# Wifi_Relay_V3.net
KiCad netlist of a schematic drawn in Altium Designer
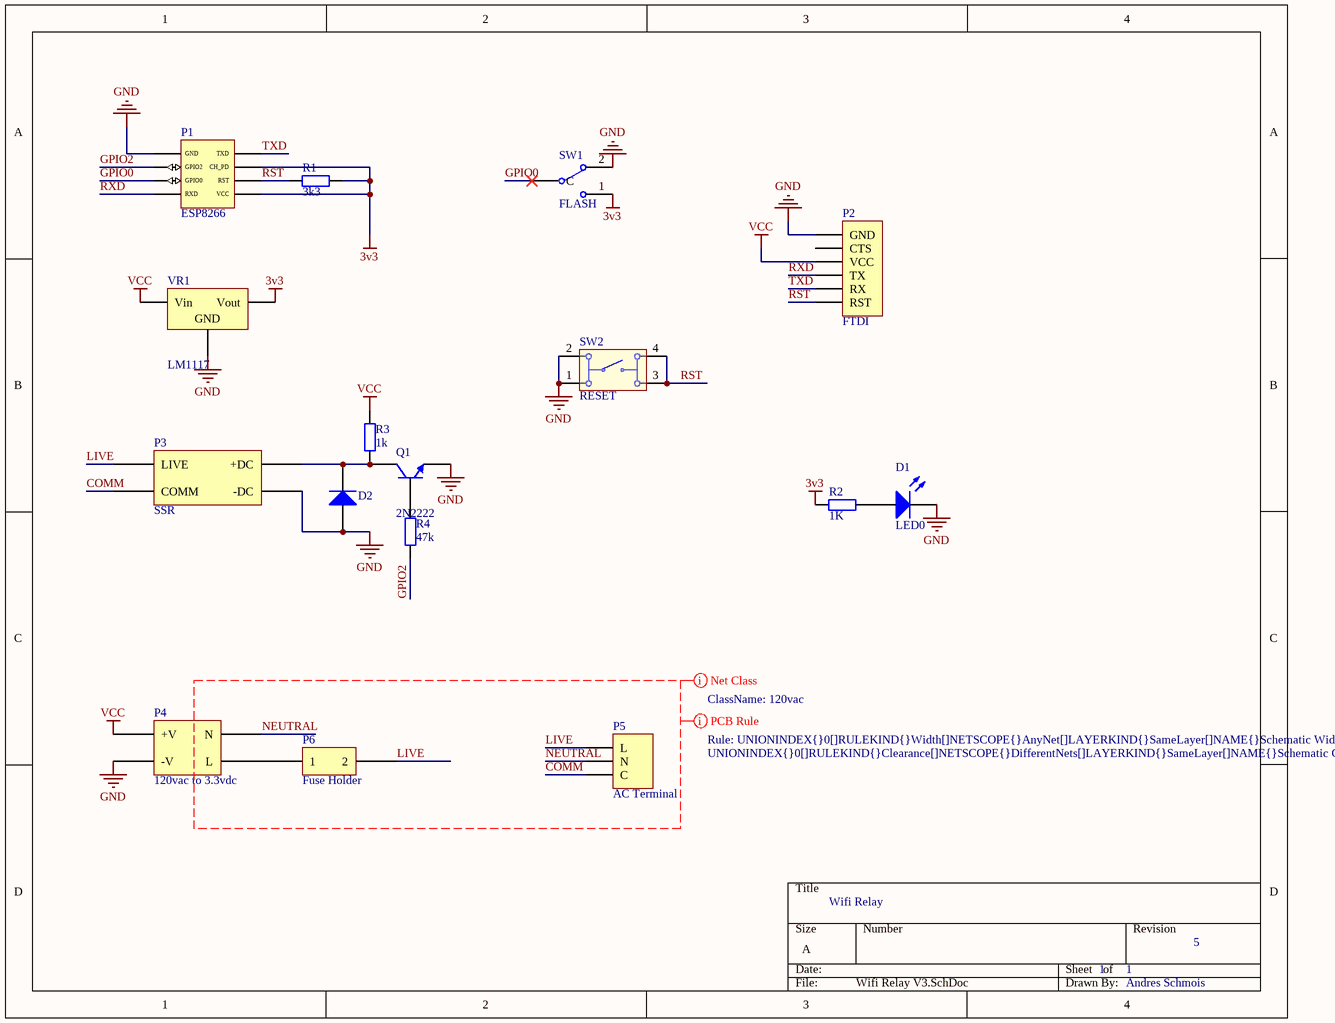
[diagram p0: Wifi Relay V3.SchDoc]

(export (version "E")
  (design (tool "Eeschema 10.0.6"))
  (components
    (comp (ref "D1")
      (value "LED0")
      (footprint "LED")
      (description "Typical INFRARED GaAs LED")
      (fields (field (name "PUBLISHER") "Altium Limited"))
      (libsource (lib "Miscellaneous Devices") (part "LED0"))
    )
    (comp (ref "D2")
      (value "Diode")
      (footprint "DO-35")
      (description "High Conductance Fast Diode")
      (fields (field (name "PUBLISHER") "Altium Limited"))
      (libsource (lib "Miscellaneous Devices") (part "Diode 1N914"))
    )
    (comp (ref "P1")
      (value "ESP8266")
      (footprint "Wifi Relay V3:ESP8266")
      (description "Header, 4-Pin, Dual row")
      (fields (field (name "PUBLISHER") "Altium Limited"))
      (libsource (lib "Miscellaneous Connectors") (part "Header 4X2A"))
    )
    (comp (ref "P2")
      (value "FTDI")
      (footprint "HDR1X6")
      (description "Header, 6-Pin")
      (fields (field (name "PUBLISHER") "Altium Limited"))
      (libsource (lib "Miscellaneous Connectors") (part "Header 6"))
    )
    (comp (ref "P3") (value "SSR") (footprint "Relay") (libsource (lib "Wifi Relay V3") (part "SSR")))
    (comp (ref "P4")
      (value "120vac to 3.3vdc")
      (footprint "120vac to 3.3vdc")
      (libsource (lib "Wifi Relay V3") (part "120vac to 3.3vdc"))
    )
    (comp (ref "P5")
      (value "AC Terminal")
      (footprint "Wifi Relay V3:AC Terminal")
      (description "Header, 3-Pin")
      (fields (field (name "PUBLISHER") "Altium Limited"))
      (libsource (lib "Miscellaneous Connectors") (part "Header 3"))
    )
    (comp (ref "P6")
      (value "Fuse Holder")
      (footprint "Fuse Holder")
      (libsource (lib "Wifi Relay V3") (part "Fuse Holder"))
    )
    (comp (ref "Q1")
      (value "2N2222")
      (footprint "TO-92A")
      (description "NPN 2N2222")
      (fields (field (name "PUBLISHER") "Altium Limited"))
      (libsource (lib "Miscellaneous Devices") (part "2N3904"))
    )
    (comp (ref "R1")
      (value "3k3")
      (footprint "AXIAL-0.4")
      (description "Resistor")
      (fields (field (name "PUBLISHER") "Altium Limited"))
      (libsource (lib "Miscellaneous Devices") (part "Res2"))
    )
    (comp (ref "R2")
      (value "1K")
      (footprint "AXIAL-0.4")
      (description "Resistor")
      (fields (field (name "PUBLISHER") "Altium Limited"))
      (libsource (lib "Miscellaneous Devices") (part "Res2"))
    )
    (comp (ref "R3")
      (value "1k")
      (footprint "AXIAL-0.4")
      (description "Resistor")
      (fields (field (name "PUBLISHER") "Altium Limited"))
      (libsource (lib "") (part "Res2_1"))
    )
    (comp (ref "R4")
      (value "47k")
      (footprint "AXIAL-0.4")
      (description "Resistor")
      (fields (field (name "PUBLISHER") "Altium Limited"))
      (libsource (lib "") (part "Res2_1"))
    )
    (comp (ref "SW1")
      (value "FLASH")
      (footprint "SWITCH")
      (description "SPDT Subminiature Toggle Switch, Right Angle Mounting, Vertical Actuation")
      (fields (field (name "PUBLISHER") "Altium Limited"))
      (libsource (lib "Miscellaneous Devices") (part "SW-SPDT"))
    )
    (comp (ref "SW2")
      (value "RESET")
      (footprint "MINI PUSH BUTTON")
      (description "WS-TATV THT Tact Switch 12X12 mm")
      (fields
        (field (name "MANUFACTURER") "Würth Elektronik eiSos GmbH & Co.KG")
        (field (name "PARTNO") "430456085736")
        (field (name "CREAT BY") "Karrer Zheng")
      )
      (libsource (lib "Tact_Switches_rev15a") (part "WE-Tact Switches WS-TATV 430456085736"))
    )
    (comp (ref "VR1")
      (value "LM1117")
      (footprint "Miscellaneous Devices:TO-220-AB")
      (description "Voltage Regulator")
      (fields (field (name "PUBLISHER") "Altium Limited"))
      (libsource (lib "Miscellaneous Devices") (part "Volt Reg"))
    )
  )
  (nets
    (net (code "1") (name "/COMM") (class "Default")
      (node (ref "P3") (pin "1") (pinfunction "COMM_1") (pintype "passive"))
      (node (ref "P5") (pin "3") (pinfunction "C_3") (pintype "passive"))
    )
    (net (code "2") (name "/GPIO0") (class "Default")
      (node (ref "P1") (pin "3") (pinfunction "GPIO0_3") (pintype "bidirectional"))
      (node (ref "SW1") (pin "C") (pinfunction "C_C") (pintype "passive"))
    )
    (net (code "3") (name "/GPIO2") (class "Default")
      (node (ref "P1") (pin "2") (pinfunction "GPIO2_2") (pintype "bidirectional"))
      (node (ref "R4") (pin "1") (pinfunction "1_1") (pintype "passive"))
    )
    (net (code "4") (name "/LIVE") (class "Default")
      (node (ref "P3") (pin "2") (pinfunction "LIVE_2") (pintype "passive"))
      (node (ref "P5") (pin "1") (pinfunction "L_1") (pintype "passive"))
      (node (ref "P6") (pin "2") (pinfunction "2_2") (pintype "passive"))
    )
    (net (code "5") (name "/NEUTRAL") (class "Default")
      (node (ref "P4") (pin "N") (pinfunction "N_N") (pintype "passive"))
      (node (ref "P5") (pin "2") (pinfunction "N_2") (pintype "passive"))
    )
    (net (code "6") (name "/RST") (class "Default")
      (node (ref "P1") (pin "7") (pinfunction "RST_7") (pintype "passive"))
      (node (ref "P2") (pin "6") (pinfunction "RST_6") (pintype "passive"))
      (node (ref "R1") (pin "1") (pinfunction "1_1") (pintype "passive"))
      (node (ref "SW2") (pin "3") (pinfunction "3_3") (pintype "passive"))
      (node (ref "SW2") (pin "4") (pinfunction "4_4") (pintype "passive"))
    )
    (net (code "7") (name "/RXD") (class "Default")
      (node (ref "P1") (pin "4") (pinfunction "RXD_4") (pintype "passive"))
      (node (ref "P2") (pin "4") (pinfunction "TX_4") (pintype "passive"))
    )
    (net (code "8") (name "/TXD") (class "Default")
      (node (ref "P1") (pin "5") (pinfunction "TXD_5") (pintype "passive"))
      (node (ref "P2") (pin "5") (pinfunction "RX_5") (pintype "passive"))
    )
    (net (code "9") (name "3v3") (class "Default")
      (node (ref "P1") (pin "6") (pinfunction "CH_PD_6") (pintype "passive"))
      (node (ref "P1") (pin "8") (pinfunction "VCC_8") (pintype "power_in"))
      (node (ref "R1") (pin "2") (pinfunction "2_2") (pintype "passive"))
      (node (ref "R2") (pin "1") (pinfunction "1_1") (pintype "passive"))
      (node (ref "SW1") (pin "1") (pinfunction "1_1") (pintype "passive"))
      (node (ref "VR1") (pin "2") (pinfunction "Vout_2") (pintype "passive"))
    )
    (net (code "10") (name "GND") (class "Default")
      (node (ref "D1") (pin "2") (pinfunction "K_2") (pintype "passive"))
      (node (ref "D2") (pin "1") (pinfunction "A_1") (pintype "passive"))
      (node (ref "P1") (pin "1") (pinfunction "GND_1") (pintype "power_in"))
      (node (ref "P2") (pin "1") (pinfunction "GND_1") (pintype "power_in"))
      (node (ref "P3") (pin "4") (pinfunction "-DC_4") (pintype "passive"))
      (node (ref "P4") (pin "-V") (pinfunction "-V_-V") (pintype "passive"))
      (node (ref "Q1") (pin "1") (pinfunction "E_1") (pintype "passive"))
      (node (ref "SW1") (pin "2") (pinfunction "2_2") (pintype "passive"))
      (node (ref "SW2") (pin "1") (pinfunction "1_1") (pintype "passive"))
      (node (ref "SW2") (pin "2") (pinfunction "2_2") (pintype "passive"))
      (node (ref "VR1") (pin "1") (pinfunction "GND_1") (pintype "passive"))
    )
    (net (code "11") (name "Net-(D1-A)") (class "Default")
      (node (ref "D1") (pin "1") (pinfunction "A_1") (pintype "passive"))
      (node (ref "R2") (pin "2") (pinfunction "2_2") (pintype "passive"))
    )
    (net (code "12") (name "Net-(D2-K)") (class "Default")
      (node (ref "D2") (pin "2") (pinfunction "K_2") (pintype "passive"))
      (node (ref "P3") (pin "3") (pinfunction "+DC_3") (pintype "passive"))
      (node (ref "Q1") (pin "3") (pinfunction "C_3") (pintype "passive"))
      (node (ref "R3") (pin "1") (pinfunction "1_1") (pintype "passive"))
    )
    (net (code "13") (name "Net-(P4-PadL)") (class "Default")
      (node (ref "P4") (pin "L") (pinfunction "L_L") (pintype "passive"))
      (node (ref "P6") (pin "1") (pinfunction "1_1") (pintype "passive"))
    )
    (net (code "14") (name "Net-(Q1-B)") (class "Default")
      (node (ref "Q1") (pin "2") (pinfunction "B_2") (pintype "passive"))
      (node (ref "R4") (pin "2") (pinfunction "2_2") (pintype "passive"))
    )
    (net (code "15") (name "VCC") (class "Default")
      (node (ref "P2") (pin "3") (pinfunction "VCC_3") (pintype "power_in"))
      (node (ref "P4") (pin "+V") (pinfunction "+V_+V") (pintype "passive"))
      (node (ref "R3") (pin "2") (pinfunction "2_2") (pintype "passive"))
      (node (ref "VR1") (pin "3") (pinfunction "Vin_3") (pintype "passive"))
    )
    (net (code "16") (name "unconnected-(P2-CTS-Pad2)") (class "Default")
      (node (ref "P2") (pin "2") (pinfunction "CTS_2") (pintype "passive"))
    )
  )
)
